# sensor.net
KiCad netlist of a schematic drawn in Altium Designer
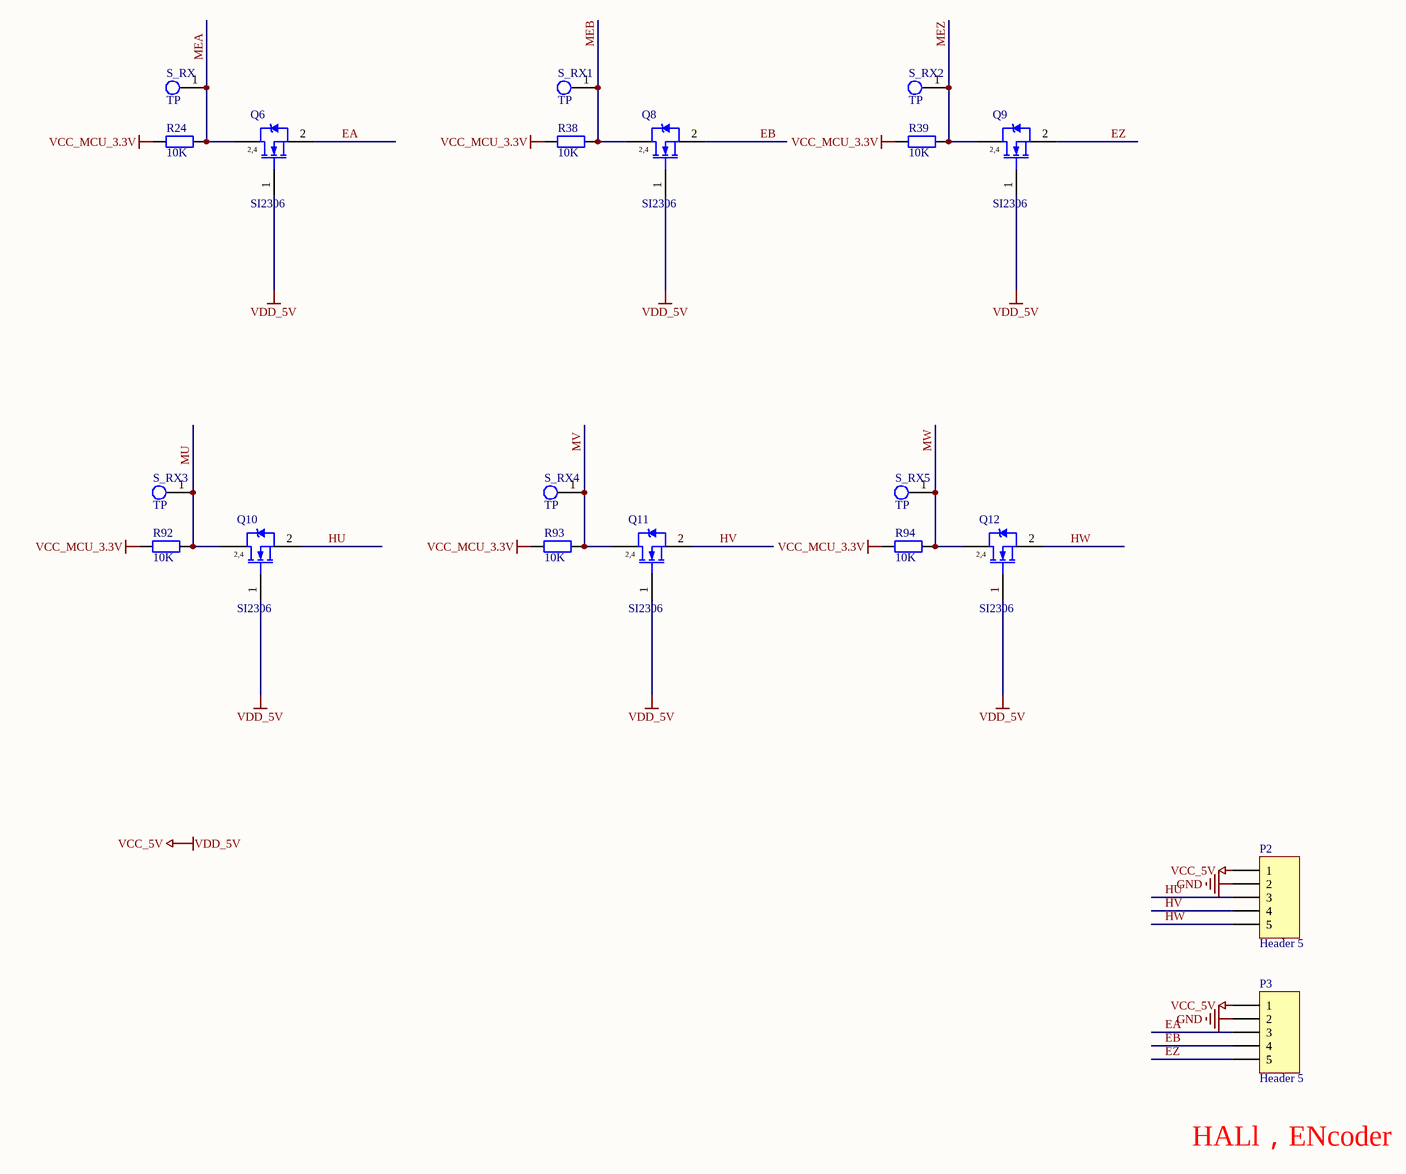
[diagram p0: sensor.SchDoc]

(export (version "E")
  (design (tool "Eeschema 10.0.6"))
  (components
    (comp (ref "P2")
      (value "Header 5")
      (footprint "HDR1X5")
      (description "Header, 5-Pin")
      (fields (field (name "PUBLISHER") "Altium Limited"))
      (libsource (lib "Miscellaneous Connectors") (part "Header 5"))
    )
    (comp (ref "P3")
      (value "Header 5")
      (footprint "HDR1X5")
      (description "Header, 5-Pin")
      (fields (field (name "PUBLISHER") "Altium Limited"))
      (libsource (lib "Miscellaneous Connectors") (part "Header 5"))
    )
    (comp (ref "Q6")
      (value "SI2306")
      (footprint "Pcblib_20110825:SOT23-3")
      (description "BUK92150-55A")
      (fields (field (name "PUBLISHER") "Altium Limited"))
      (libsource (lib "Schlib1") (part "BUK92150-55A"))
    )
    (comp (ref "Q8")
      (value "SI2306")
      (footprint "SOT23-3")
      (description "BUK92150-55A")
      (fields (field (name "PUBLISHER") "Altium Limited"))
      (libsource (lib "Schlib1") (part "BUK92150-55A"))
    )
    (comp (ref "Q9")
      (value "SI2306")
      (footprint "Pcblib_20110825:SOT23-3")
      (description "BUK92150-55A")
      (fields (field (name "PUBLISHER") "Altium Limited"))
      (libsource (lib "Schlib1") (part "BUK92150-55A"))
    )
    (comp (ref "Q10")
      (value "SI2306")
      (footprint "Pcblib_20110825:SOT23-3")
      (description "BUK92150-55A")
      (fields (field (name "PUBLISHER") "Altium Limited"))
      (libsource (lib "Schlib1") (part "BUK92150-55A"))
    )
    (comp (ref "Q11")
      (value "SI2306")
      (footprint "Pcblib_20110825:SOT23-3")
      (description "BUK92150-55A")
      (fields (field (name "PUBLISHER") "Altium Limited"))
      (libsource (lib "Schlib1") (part "BUK92150-55A"))
    )
    (comp (ref "Q12")
      (value "SI2306")
      (footprint "Pcblib_20110825:SOT23-3")
      (description "BUK92150-55A")
      (fields (field (name "PUBLISHER") "Altium Limited"))
      (libsource (lib "Schlib1") (part "BUK92150-55A"))
    )
    (comp (ref "R24")
      (value "10K")
      (footprint "Pcblib_20110825:0603R")
      (description "Resistor")
      (fields (field (name "PUBLISHER") "Altium Limited"))
      (libsource (lib "Miscellaneous Devices") (part "Res2"))
    )
    (comp (ref "R38")
      (value "10K")
      (footprint "Pcblib_20110825:0603R")
      (description "Resistor")
      (fields (field (name "PUBLISHER") "Altium Limited"))
      (libsource (lib "Miscellaneous Devices") (part "Res2"))
    )
    (comp (ref "R39")
      (value "10K")
      (footprint "Pcblib_20110825:0603R")
      (description "Resistor")
      (fields (field (name "PUBLISHER") "Altium Limited"))
      (libsource (lib "Miscellaneous Devices") (part "Res2"))
    )
    (comp (ref "R92")
      (value "10K")
      (footprint "Pcblib_20110825:0603R")
      (description "Resistor")
      (fields (field (name "PUBLISHER") "Altium Limited"))
      (libsource (lib "Miscellaneous Devices") (part "Res2"))
    )
    (comp (ref "R93")
      (value "10K")
      (footprint "Pcblib_20110825:0603R")
      (description "Resistor")
      (fields (field (name "PUBLISHER") "Altium Limited"))
      (libsource (lib "Miscellaneous Devices") (part "Res2"))
    )
    (comp (ref "R94")
      (value "10K")
      (footprint "Pcblib_20110825:0603R")
      (description "Resistor")
      (fields (field (name "PUBLISHER") "Altium Limited"))
      (libsource (lib "Miscellaneous Devices") (part "Res2"))
    )
    (comp (ref "S_RX")
      (value "TP")
      (footprint "Pcblib_20110825:TPD")
      (libsource (lib "Schlib_20110825") (part "TP"))
    )
    (comp (ref "S_RX1")
      (value "TP")
      (footprint "Pcblib_20110825:TPD")
      (libsource (lib "Schlib_20110825") (part "TP"))
    )
    (comp (ref "S_RX2")
      (value "TP")
      (footprint "Pcblib_20110825:TPD")
      (libsource (lib "Schlib_20110825") (part "TP"))
    )
    (comp (ref "S_RX3")
      (value "TP")
      (footprint "Pcblib_20110825:TPD")
      (libsource (lib "Schlib_20110825") (part "TP"))
    )
    (comp (ref "S_RX4")
      (value "TP")
      (footprint "Pcblib_20110825:TPD")
      (libsource (lib "Schlib_20110825") (part "TP"))
    )
    (comp (ref "S_RX5")
      (value "TP")
      (footprint "Pcblib_20110825:TPD")
      (libsource (lib "Schlib_20110825") (part "TP"))
    )
  )
  (nets
    (net (code "1") (name "/EA") (class "Default")
      (node (ref "P3") (pin "3") (pinfunction "3_3") (pintype "passive"))
      (node (ref "Q6") (pin "2") (pinfunction "S_2") (pintype "passive"))
    )
    (net (code "2") (name "/EB") (class "Default")
      (node (ref "P3") (pin "4") (pinfunction "4_4") (pintype "passive"))
      (node (ref "Q8") (pin "2") (pinfunction "S_2") (pintype "passive"))
    )
    (net (code "3") (name "/EZ") (class "Default")
      (node (ref "P3") (pin "5") (pinfunction "5_5") (pintype "passive"))
      (node (ref "Q9") (pin "2") (pinfunction "S_2") (pintype "passive"))
    )
    (net (code "4") (name "/HU") (class "Default")
      (node (ref "P2") (pin "3") (pinfunction "3_3") (pintype "passive"))
      (node (ref "Q10") (pin "2") (pinfunction "S_2") (pintype "passive"))
    )
    (net (code "5") (name "/HV") (class "Default")
      (node (ref "P2") (pin "4") (pinfunction "4_4") (pintype "passive"))
      (node (ref "Q11") (pin "2") (pinfunction "S_2") (pintype "passive"))
    )
    (net (code "6") (name "/HW") (class "Default")
      (node (ref "P2") (pin "5") (pinfunction "5_5") (pintype "passive"))
      (node (ref "Q12") (pin "2") (pinfunction "S_2") (pintype "passive"))
    )
    (net (code "7") (name "/MEA") (class "Default")
      (node (ref "Q6") (pin "3") (pinfunction "D_3") (pintype "passive"))
      (node (ref "R24") (pin "2") (pinfunction "2_2") (pintype "passive"))
      (node (ref "S_RX") (pin "1") (pintype "passive"))
    )
    (net (code "8") (name "/MEB") (class "Default")
      (node (ref "Q8") (pin "3") (pinfunction "D_3") (pintype "passive"))
      (node (ref "R38") (pin "2") (pinfunction "2_2") (pintype "passive"))
      (node (ref "S_RX1") (pin "1") (pintype "passive"))
    )
    (net (code "9") (name "/MEZ") (class "Default")
      (node (ref "Q9") (pin "3") (pinfunction "D_3") (pintype "passive"))
      (node (ref "R39") (pin "2") (pinfunction "2_2") (pintype "passive"))
      (node (ref "S_RX2") (pin "1") (pintype "passive"))
    )
    (net (code "10") (name "/MU") (class "Default")
      (node (ref "Q10") (pin "3") (pinfunction "D_3") (pintype "passive"))
      (node (ref "R92") (pin "2") (pinfunction "2_2") (pintype "passive"))
      (node (ref "S_RX3") (pin "1") (pintype "passive"))
    )
    (net (code "11") (name "/MV") (class "Default")
      (node (ref "Q11") (pin "3") (pinfunction "D_3") (pintype "passive"))
      (node (ref "R93") (pin "2") (pinfunction "2_2") (pintype "passive"))
      (node (ref "S_RX4") (pin "1") (pintype "passive"))
    )
    (net (code "12") (name "/MW") (class "Default")
      (node (ref "Q12") (pin "3") (pinfunction "D_3") (pintype "passive"))
      (node (ref "R94") (pin "2") (pinfunction "2_2") (pintype "passive"))
      (node (ref "S_RX5") (pin "1") (pintype "passive"))
    )
    (net (code "13") (name "GND") (class "Default")
      (node (ref "P2") (pin "2") (pinfunction "2_2") (pintype "passive"))
      (node (ref "P3") (pin "2") (pinfunction "2_2") (pintype "passive"))
    )
    (net (code "14") (name "VCC_5V") (class "Default")
      (node (ref "P2") (pin "1") (pinfunction "1_1") (pintype "passive"))
      (node (ref "P3") (pin "1") (pinfunction "1_1") (pintype "passive"))
      (node (ref "Q10") (pin "1") (pinfunction "G_1") (pintype "passive"))
      (node (ref "Q11") (pin "1") (pinfunction "G_1") (pintype "passive"))
      (node (ref "Q12") (pin "1") (pinfunction "G_1") (pintype "passive"))
      (node (ref "Q6") (pin "1") (pinfunction "G_1") (pintype "passive"))
      (node (ref "Q8") (pin "1") (pinfunction "G_1") (pintype "passive"))
      (node (ref "Q9") (pin "1") (pinfunction "G_1") (pintype "passive"))
    )
    (net (code "15") (name "VCC_MCU_3.3V") (class "Default")
      (node (ref "R24") (pin "1") (pinfunction "1_1") (pintype "passive"))
      (node (ref "R38") (pin "1") (pinfunction "1_1") (pintype "passive"))
      (node (ref "R39") (pin "1") (pinfunction "1_1") (pintype "passive"))
      (node (ref "R92") (pin "1") (pinfunction "1_1") (pintype "passive"))
      (node (ref "R93") (pin "1") (pinfunction "1_1") (pintype "passive"))
      (node (ref "R94") (pin "1") (pinfunction "1_1") (pintype "passive"))
    )
  )
)
